# Vinduno-R-22-3-15.net
KiCad netlist of a schematic drawn in EAGLE
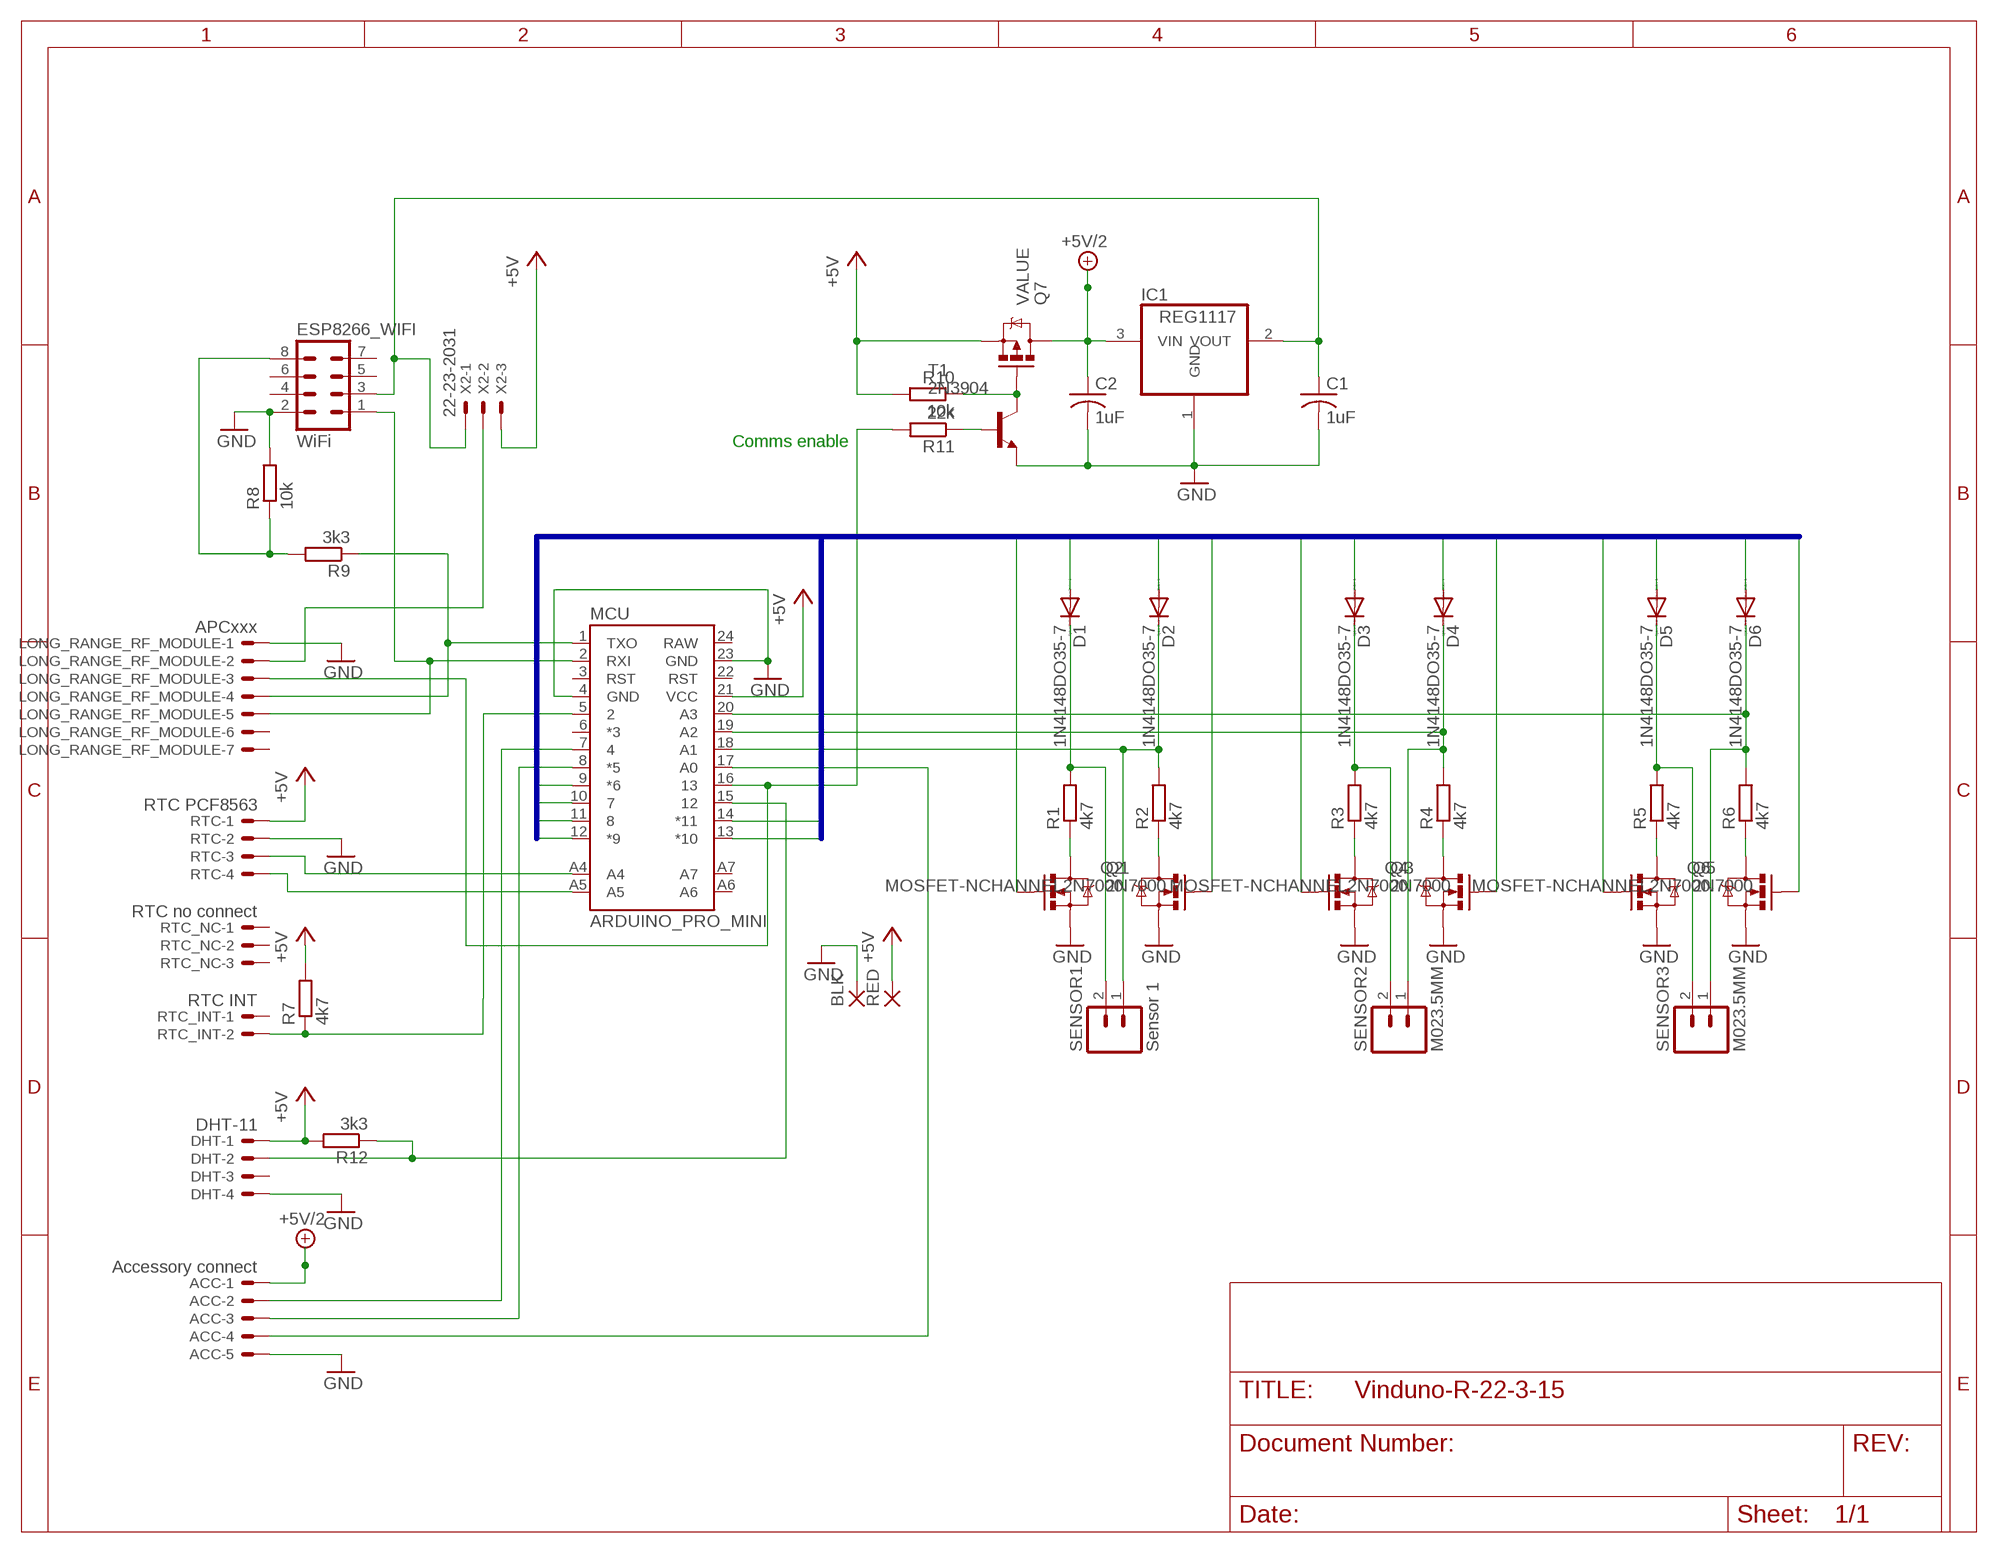
[diagram p0: schematic, sheet 1]

(export (version "E")
  (design (tool "Eeschema 10.0.6"))
  (components
    (comp (ref "ACC")
      (value "Accessory connect")
      (footprint "eagle-import:22-23-2051")
      (fields (field (name "MF") "MOLEX") (field (name "MPN") "22-23-2051"))
      (libsource (lib "eagle-import") (part "22-23-2051"))
    )
    (comp (ref "BLK")
      (value "WIREPAD2,54/0,9")
      (footprint "eagle-import:2,54_0,9")
      (libsource (lib "eagle-import") (part "WIREPAD2,54/0,9"))
    )
    (comp (ref "C1")
      (value "1uF")
      (footprint "eagle-import:C025-030X050")
      (libsource (lib "eagle-import") (part "C-US025-030X050"))
    )
    (comp (ref "C2")
      (value "1uF")
      (footprint "eagle-import:C025-030X050")
      (libsource (lib "eagle-import") (part "C-US025-030X050"))
    )
    (comp (ref "D1")
      (value "1N4148DO35-7")
      (footprint "eagle-import:DO35-7")
      (libsource (lib "eagle-import") (part "1N4148DO35-7"))
    )
    (comp (ref "D2")
      (value "1N4148DO35-7")
      (footprint "eagle-import:DO35-7")
      (libsource (lib "eagle-import") (part "1N4148DO35-7"))
    )
    (comp (ref "D3")
      (value "1N4148DO35-7")
      (footprint "eagle-import:DO35-7")
      (libsource (lib "eagle-import") (part "1N4148DO35-7"))
    )
    (comp (ref "D4")
      (value "1N4148DO35-7")
      (footprint "eagle-import:DO35-7")
      (libsource (lib "eagle-import") (part "1N4148DO35-7"))
    )
    (comp (ref "D5")
      (value "1N4148DO35-7")
      (footprint "eagle-import:DO35-7")
      (libsource (lib "eagle-import") (part "1N4148DO35-7"))
    )
    (comp (ref "D6")
      (value "1N4148DO35-7")
      (footprint "eagle-import:DO35-7")
      (libsource (lib "eagle-import") (part "1N4148DO35-7"))
    )
    (comp (ref "DHT")
      (value "DHT-11")
      (footprint "eagle-import:22-23-2041")
      (fields (field (name "MF") "MOLEX") (field (name "MPN") "22-23-2041"))
      (libsource (lib "eagle-import") (part "22-23-2041"))
    )
    (comp (ref "ESP8266_WIFI")
      (value "WiFi")
      (footprint "eagle-import:MA04-2")
      (libsource (lib "eagle-import") (part "MA04-2"))
    )
    (comp (ref "IC1")
      (value "REG1117")
      (footprint "eagle-import:SOT223")
      (libsource (lib "eagle-import") (part "REG1117"))
    )
    (comp (ref "LONG_RANGE_RF_MODULE")
      (value "APCxxx")
      (footprint "eagle-import:22-23-2071")
      (fields (field (name "MF") "MOLEX") (field (name "MPN") "22-23-2071"))
      (libsource (lib "eagle-import") (part "22-23-2071"))
    )
    (comp (ref "MCU")
      (value "ARDUINO_PRO_MINI")
      (footprint "eagle-import:ARDUINO_PRO_MINI")
      (libsource (lib "eagle-import") (part "ARDUINO_PRO_MINI"))
    )
    (comp (ref "Q1")
      (value "2N7000")
      (footprint "eagle-import:TO-92")
      (libsource (lib "eagle-import") (part "MOSFET-NCHANNEL2N7000"))
    )
    (comp (ref "Q2")
      (value "MOSFET-NCHANNEL2N7000")
      (footprint "eagle-import:TO-92")
      (libsource (lib "eagle-import") (part "MOSFET-NCHANNEL2N7000"))
    )
    (comp (ref "Q3")
      (value "2N7000")
      (footprint "eagle-import:TO-92")
      (libsource (lib "eagle-import") (part "MOSFET-NCHANNEL2N7000"))
    )
    (comp (ref "Q4")
      (value "MOSFET-NCHANNEL2N7000")
      (footprint "eagle-import:TO-92")
      (libsource (lib "eagle-import") (part "MOSFET-NCHANNEL2N7000"))
    )
    (comp (ref "Q5")
      (value "2N7000")
      (footprint "eagle-import:TO-92")
      (libsource (lib "eagle-import") (part "MOSFET-NCHANNEL2N7000"))
    )
    (comp (ref "Q6")
      (value "MOSFET-NCHANNEL2N7000")
      (footprint "eagle-import:TO-92")
      (libsource (lib "eagle-import") (part "MOSFET-NCHANNEL2N7000"))
    )
    (comp (ref "Q7")
      (value "AO3401")
      (footprint "eagle-import:SOT23-3")
      (libsource (lib "eagle-import") (part "MOSFET-PCHANNEL"))
    )
    (comp (ref "R1")
      (value "4k7")
      (footprint "eagle-import:0204_7")
      (libsource (lib "eagle-import") (part "R-EU_0204/7"))
    )
    (comp (ref "R2")
      (value "4k7")
      (footprint "eagle-import:0204_7")
      (libsource (lib "eagle-import") (part "R-EU_0204/7"))
    )
    (comp (ref "R3")
      (value "4k7")
      (footprint "eagle-import:0204_7")
      (libsource (lib "eagle-import") (part "R-EU_0204/7"))
    )
    (comp (ref "R4")
      (value "4k7")
      (footprint "eagle-import:0204_7")
      (libsource (lib "eagle-import") (part "R-EU_0204/7"))
    )
    (comp (ref "R5")
      (value "4k7")
      (footprint "eagle-import:0204_7")
      (libsource (lib "eagle-import") (part "R-EU_0204/7"))
    )
    (comp (ref "R6")
      (value "4k7")
      (footprint "eagle-import:0204_7")
      (libsource (lib "eagle-import") (part "R-EU_0204/7"))
    )
    (comp (ref "R7")
      (value "4k7")
      (footprint "eagle-import:0204_7")
      (libsource (lib "eagle-import") (part "R-EU_0204/7"))
    )
    (comp (ref "R8")
      (value "10k")
      (footprint "eagle-import:0204_7")
      (libsource (lib "eagle-import") (part "R-EU_0204/7"))
    )
    (comp (ref "R9")
      (value "3k3")
      (footprint "eagle-import:0204_7")
      (libsource (lib "eagle-import") (part "R-EU_0204/7"))
    )
    (comp (ref "R10")
      (value "10k")
      (footprint "eagle-import:0204_7")
      (libsource (lib "eagle-import") (part "R-EU_0204/7"))
    )
    (comp (ref "R11")
      (value "22k")
      (footprint "eagle-import:0204_7")
      (libsource (lib "eagle-import") (part "R-EU_0204/7"))
    )
    (comp (ref "R12")
      (value "3k3")
      (footprint "eagle-import:0204_7")
      (libsource (lib "eagle-import") (part "R-EU_0204/7"))
    )
    (comp (ref "RED")
      (value "WIREPAD2,54/0,9")
      (footprint "eagle-import:2,54_0,9")
      (libsource (lib "eagle-import") (part "WIREPAD2,54/0,9"))
    )
    (comp (ref "RTC")
      (value "RTC PCF8563")
      (footprint "eagle-import:22-23-2041")
      (fields (field (name "MF") "MOLEX") (field (name "MPN") "22-23-2041") (field (name "MPN_1") "RTC"))
      (libsource (lib "eagle-import") (part "22-23-2041"))
    )
    (comp (ref "RTC_INT")
      (value "RTC INT")
      (footprint "eagle-import:22-23-2021")
      (fields (field (name "MF") "MOLEX") (field (name "MPN") "22-23-2021"))
      (libsource (lib "eagle-import") (part "22-23-2021"))
    )
    (comp (ref "RTC_NC")
      (value "RTC no connect")
      (footprint "eagle-import:22-23-2031")
      (fields (field (name "MF") "MOLEX") (field (name "MPN") "22-23-2031"))
      (libsource (lib "eagle-import") (part "22-23-2031"))
    )
    (comp (ref "SENSOR1")
      (value "Sensor 1")
      (footprint "eagle-import:SCREWTERMINAL-3.5MM-2")
      (libsource (lib "eagle-import") (part "M023.5MM"))
    )
    (comp (ref "SENSOR2")
      (value "M023.5MM")
      (footprint "eagle-import:SCREWTERMINAL-3.5MM-2")
      (libsource (lib "eagle-import") (part "M023.5MM"))
    )
    (comp (ref "SENSOR3")
      (value "M023.5MM")
      (footprint "eagle-import:SCREWTERMINAL-3.5MM-2")
      (libsource (lib "eagle-import") (part "M023.5MM"))
    )
    (comp (ref "T1")
      (value "2N3904")
      (footprint "eagle-import:TO92")
      (libsource (lib "eagle-import") (part "2N3904"))
    )
    (comp (ref "X2")
      (value "22-23-2031")
      (footprint "eagle-import:22-23-2031")
      (fields (field (name "MF") "MOLEX"))
      (libsource (lib "eagle-import") (part "22-23-2031"))
    )
  )
  (nets
    (net (code "1") (name "+5V") (class "Default")
      (node (ref "DHT") (pin "1") (pinfunction "S_1") (pintype "passive"))
      (node (ref "MCU") (pin "21") (pinfunction "VCC_21") (pintype "bidirectional"))
      (node (ref "Q7") (pin "2") (pinfunction "S_2") (pintype "passive"))
      (node (ref "R10") (pin "2") (pinfunction "2_2") (pintype "passive"))
      (node (ref "R12") (pin "2") (pinfunction "2_2") (pintype "passive"))
      (node (ref "R7") (pin "2") (pinfunction "2_2") (pintype "passive"))
      (node (ref "RED") (pin "1") (pinfunction "P_1") (pintype "passive"))
      (node (ref "RTC") (pin "1") (pinfunction "S_1") (pintype "passive"))
      (node (ref "X2") (pin "3") (pinfunction "S_3") (pintype "passive"))
    )
    (net (code "2") (name "+5V{slash}2") (class "Default")
      (node (ref "ACC") (pin "1") (pinfunction "S_1") (pintype "passive"))
      (node (ref "C2") (pin "1") (pinfunction "1_1") (pintype "passive"))
      (node (ref "IC1") (pin "3") (pinfunction "VIN_3") (pintype "input"))
      (node (ref "Q7") (pin "3") (pinfunction "D_3") (pintype "passive"))
    )
    (net (code "3") (name "/DIODE1") (class "Default")
      (node (ref "D1") (pin "A") (pinfunction "A_A") (pintype "passive"))
      (node (ref "MCU") (pin "9") (pinfunction "*6_9") (pintype "bidirectional"))
      (node (ref "Q2") (pin "2") (pinfunction "G_2") (pintype "passive"))
    )
    (net (code "4") (name "/DIODE2") (class "Default")
      (node (ref "D2") (pin "A") (pinfunction "A_A") (pintype "passive"))
      (node (ref "MCU") (pin "10") (pinfunction "7_10") (pintype "bidirectional"))
      (node (ref "Q1") (pin "2") (pinfunction "G_2") (pintype "passive"))
    )
    (net (code "5") (name "/DIODE3") (class "Default")
      (node (ref "D3") (pin "A") (pinfunction "A_A") (pintype "passive"))
      (node (ref "MCU") (pin "11") (pinfunction "8_11") (pintype "bidirectional"))
      (node (ref "Q4") (pin "2") (pinfunction "G_2") (pintype "passive"))
    )
    (net (code "6") (name "/DIODE4") (class "Default")
      (node (ref "D4") (pin "A") (pinfunction "A_A") (pintype "passive"))
      (node (ref "MCU") (pin "12") (pinfunction "*9_12") (pintype "bidirectional"))
      (node (ref "Q3") (pin "2") (pinfunction "G_2") (pintype "passive"))
    )
    (net (code "7") (name "/DIODE5") (class "Default")
      (node (ref "D5") (pin "A") (pinfunction "A_A") (pintype "passive"))
      (node (ref "MCU") (pin "13") (pinfunction "*10_13") (pintype "bidirectional"))
      (node (ref "Q6") (pin "2") (pinfunction "G_2") (pintype "passive"))
    )
    (net (code "8") (name "/DIODE6") (class "Default")
      (node (ref "D6") (pin "A") (pinfunction "A_A") (pintype "passive"))
      (node (ref "MCU") (pin "14") (pinfunction "*11_14") (pintype "bidirectional"))
      (node (ref "Q5") (pin "2") (pinfunction "G_2") (pintype "passive"))
    )
    (net (code "9") (name "GND") (class "Default")
      (node (ref "ACC") (pin "5") (pinfunction "S_5") (pintype "passive"))
      (node (ref "BLK") (pin "1") (pinfunction "P_1") (pintype "passive"))
      (node (ref "C1") (pin "2") (pinfunction "2_2") (pintype "passive"))
      (node (ref "C2") (pin "2") (pinfunction "2_2") (pintype "passive"))
      (node (ref "DHT") (pin "4") (pinfunction "S_4") (pintype "passive"))
      (node (ref "ESP8266_WIFI") (pin "2") (pinfunction "2_2") (pintype "passive"))
      (node (ref "IC1") (pin "1") (pinfunction "GND_1") (pintype "power_in"))
      (node (ref "LONG_RANGE_RF_MODULE") (pin "1") (pinfunction "S_1") (pintype "passive"))
      (node (ref "MCU") (pin "23") (pinfunction "GND_23") (pintype "bidirectional"))
      (node (ref "MCU") (pin "4") (pinfunction "GND_4") (pintype "bidirectional"))
      (node (ref "Q1") (pin "1") (pinfunction "S_1") (pintype "passive"))
      (node (ref "Q2") (pin "1") (pinfunction "S_1") (pintype "passive"))
      (node (ref "Q3") (pin "1") (pinfunction "S_1") (pintype "passive"))
      (node (ref "Q4") (pin "1") (pinfunction "S_1") (pintype "passive"))
      (node (ref "Q5") (pin "1") (pinfunction "S_1") (pintype "passive"))
      (node (ref "Q6") (pin "1") (pinfunction "S_1") (pintype "passive"))
      (node (ref "R8") (pin "2") (pinfunction "2_2") (pintype "passive"))
      (node (ref "RTC") (pin "2") (pinfunction "S_2") (pintype "passive"))
      (node (ref "T1") (pin "3") (pinfunction "E_3") (pintype "passive"))
    )
    (net (code "10") (name "Net-(ACCB-S)") (class "Default")
      (node (ref "ACC") (pin "2") (pinfunction "S_2") (pintype "passive"))
      (node (ref "MCU") (pin "7") (pinfunction "4_7") (pintype "bidirectional"))
    )
    (net (code "11") (name "Net-(ACCC-S)") (class "Default")
      (node (ref "ACC") (pin "3") (pinfunction "S_3") (pintype "passive"))
      (node (ref "MCU") (pin "8") (pinfunction "*5_8") (pintype "bidirectional"))
    )
    (net (code "12") (name "Net-(ACCD-S)") (class "Default")
      (node (ref "ACC") (pin "4") (pinfunction "S_4") (pintype "passive"))
      (node (ref "MCU") (pin "17") (pinfunction "A0_17") (pintype "bidirectional"))
    )
    (net (code "13") (name "Net-(D1-PadC)") (class "Default")
      (node (ref "D1") (pin "C") (pinfunction "C_C") (pintype "passive"))
      (node (ref "R1") (pin "2") (pinfunction "2_2") (pintype "passive"))
      (node (ref "SENSOR1") (pin "2") (pinfunction "2_2") (pintype "passive"))
    )
    (net (code "14") (name "Net-(D3-PadC)") (class "Default")
      (node (ref "D3") (pin "C") (pinfunction "C_C") (pintype "passive"))
      (node (ref "R3") (pin "2") (pinfunction "2_2") (pintype "passive"))
      (node (ref "SENSOR2") (pin "2") (pinfunction "2_2") (pintype "passive"))
    )
    (net (code "15") (name "Net-(D5-PadC)") (class "Default")
      (node (ref "D5") (pin "C") (pinfunction "C_C") (pintype "passive"))
      (node (ref "R5") (pin "2") (pinfunction "2_2") (pintype "passive"))
      (node (ref "SENSOR3") (pin "2") (pinfunction "2_2") (pintype "passive"))
    )
    (net (code "16") (name "Net-(DHTB-S)") (class "Default")
      (node (ref "DHT") (pin "2") (pinfunction "S_2") (pintype "passive"))
      (node (ref "MCU") (pin "15") (pinfunction "12_15") (pintype "bidirectional"))
      (node (ref "R12") (pin "1") (pinfunction "1_1") (pintype "passive"))
    )
    (net (code "17") (name "Net-(ESP8266_WIFI-Pad8)") (class "Default")
      (node (ref "ESP8266_WIFI") (pin "8") (pinfunction "8_8") (pintype "passive"))
      (node (ref "R8") (pin "1") (pinfunction "1_1") (pintype "passive"))
      (node (ref "R9") (pin "2") (pinfunction "2_2") (pintype "passive"))
    )
    (net (code "18") (name "Net-(IC1-VOUT)") (class "Default")
      (node (ref "C1") (pin "1") (pinfunction "1_1") (pintype "passive"))
      (node (ref "ESP8266_WIFI") (pin "3") (pinfunction "3_3") (pintype "passive"))
      (node (ref "IC1") (pin "2") (pinfunction "VOUT_2") (pintype "output"))
      (node (ref "X2") (pin "1") (pinfunction "S_1") (pintype "passive"))
    )
    (net (code "19") (name "Net-(LONG_RANGE_RF_MODULEB-S)") (class "Default")
      (node (ref "LONG_RANGE_RF_MODULE") (pin "2") (pinfunction "S_2") (pintype "passive"))
      (node (ref "X2") (pin "2") (pinfunction "S_2") (pintype "passive"))
    )
    (net (code "20") (name "Net-(LONG_RANGE_RF_MODULEC-S)") (class "Default")
      (node (ref "LONG_RANGE_RF_MODULE") (pin "3") (pinfunction "S_3") (pintype "passive"))
      (node (ref "MCU") (pin "16") (pinfunction "13_16") (pintype "bidirectional"))
      (node (ref "R11") (pin "2") (pinfunction "2_2") (pintype "passive"))
    )
    (net (code "21") (name "Net-(LONG_RANGE_RF_MODULED-S)") (class "Default")
      (node (ref "LONG_RANGE_RF_MODULE") (pin "4") (pinfunction "S_4") (pintype "passive"))
      (node (ref "MCU") (pin "1") (pinfunction "TXO_1") (pintype "bidirectional"))
      (node (ref "R9") (pin "1") (pinfunction "1_1") (pintype "passive"))
    )
    (net (code "22") (name "Net-(LONG_RANGE_RF_MODULEE-S)") (class "Default")
      (node (ref "ESP8266_WIFI") (pin "1") (pinfunction "1_1") (pintype "passive"))
      (node (ref "LONG_RANGE_RF_MODULE") (pin "5") (pinfunction "S_5") (pintype "passive"))
      (node (ref "MCU") (pin "2") (pinfunction "RXI_2") (pintype "bidirectional"))
    )
    (net (code "23") (name "Net-(MCU-2)") (class "Default")
      (node (ref "MCU") (pin "5") (pinfunction "2_5") (pintype "bidirectional"))
      (node (ref "R7") (pin "1") (pinfunction "1_1") (pintype "passive"))
      (node (ref "RTC_INT") (pin "2") (pinfunction "S_2") (pintype "passive"))
    )
    (net (code "24") (name "Net-(MCU-A1)") (class "Default")
      (node (ref "D2") (pin "C") (pinfunction "C_C") (pintype "passive"))
      (node (ref "MCU") (pin "18") (pinfunction "A1_18") (pintype "bidirectional"))
      (node (ref "R2") (pin "2") (pinfunction "2_2") (pintype "passive"))
      (node (ref "SENSOR1") (pin "1") (pinfunction "1_1") (pintype "passive"))
    )
    (net (code "25") (name "Net-(MCU-A2)") (class "Default")
      (node (ref "D4") (pin "C") (pinfunction "C_C") (pintype "passive"))
      (node (ref "MCU") (pin "19") (pinfunction "A2_19") (pintype "bidirectional"))
      (node (ref "R4") (pin "2") (pinfunction "2_2") (pintype "passive"))
      (node (ref "SENSOR2") (pin "1") (pinfunction "1_1") (pintype "passive"))
    )
    (net (code "26") (name "Net-(MCU-A3)") (class "Default")
      (node (ref "D6") (pin "C") (pinfunction "C_C") (pintype "passive"))
      (node (ref "MCU") (pin "20") (pinfunction "A3_20") (pintype "bidirectional"))
      (node (ref "R6") (pin "2") (pinfunction "2_2") (pintype "passive"))
      (node (ref "SENSOR3") (pin "1") (pinfunction "1_1") (pintype "passive"))
    )
    (net (code "27") (name "Net-(Q1-D)") (class "Default")
      (node (ref "Q1") (pin "3") (pinfunction "D_3") (pintype "passive"))
      (node (ref "R1") (pin "1") (pinfunction "1_1") (pintype "passive"))
    )
    (net (code "28") (name "Net-(Q2-D)") (class "Default")
      (node (ref "Q2") (pin "3") (pinfunction "D_3") (pintype "passive"))
      (node (ref "R2") (pin "1") (pinfunction "1_1") (pintype "passive"))
    )
    (net (code "29") (name "Net-(Q3-D)") (class "Default")
      (node (ref "Q3") (pin "3") (pinfunction "D_3") (pintype "passive"))
      (node (ref "R3") (pin "1") (pinfunction "1_1") (pintype "passive"))
    )
    (net (code "30") (name "Net-(Q4-D)") (class "Default")
      (node (ref "Q4") (pin "3") (pinfunction "D_3") (pintype "passive"))
      (node (ref "R4") (pin "1") (pinfunction "1_1") (pintype "passive"))
    )
    (net (code "31") (name "Net-(Q5-D)") (class "Default")
      (node (ref "Q5") (pin "3") (pinfunction "D_3") (pintype "passive"))
      (node (ref "R5") (pin "1") (pinfunction "1_1") (pintype "passive"))
    )
    (net (code "32") (name "Net-(Q6-D)") (class "Default")
      (node (ref "Q6") (pin "3") (pinfunction "D_3") (pintype "passive"))
      (node (ref "R6") (pin "1") (pinfunction "1_1") (pintype "passive"))
    )
    (net (code "33") (name "Net-(Q7-G)") (class "Default")
      (node (ref "Q7") (pin "1") (pinfunction "G_1") (pintype "passive"))
      (node (ref "R10") (pin "1") (pinfunction "1_1") (pintype "passive"))
      (node (ref "T1") (pin "1") (pinfunction "C_1") (pintype "passive"))
    )
    (net (code "34") (name "Net-(RTCC-S)") (class "Default")
      (node (ref "MCU") (pin "A4") (pinfunction "A4_A4") (pintype "bidirectional"))
      (node (ref "RTC") (pin "3") (pinfunction "S_3") (pintype "passive"))
    )
    (net (code "35") (name "Net-(RTCD-S)") (class "Default")
      (node (ref "MCU") (pin "A5") (pinfunction "A5_A5") (pintype "bidirectional"))
      (node (ref "RTC") (pin "4") (pinfunction "S_4") (pintype "passive"))
    )
    (net (code "36") (name "Net-(T1-B)") (class "Default")
      (node (ref "R11") (pin "1") (pinfunction "1_1") (pintype "passive"))
      (node (ref "T1") (pin "2") (pinfunction "B_2") (pintype "passive"))
    )
    (net (code "37") (name "unconnected-(DHTC-S-Pad3)") (class "Default")
      (node (ref "DHT") (pin "3") (pinfunction "S_3") (pintype "passive"))
    )
    (net (code "38") (name "unconnected-(ESP8266_WIFI-Pad4)") (class "Default")
      (node (ref "ESP8266_WIFI") (pin "4") (pinfunction "4_4") (pintype "passive"))
    )
    (net (code "39") (name "unconnected-(ESP8266_WIFI-Pad5)") (class "Default")
      (node (ref "ESP8266_WIFI") (pin "5") (pinfunction "5_5") (pintype "passive"))
    )
    (net (code "40") (name "unconnected-(ESP8266_WIFI-Pad6)") (class "Default")
      (node (ref "ESP8266_WIFI") (pin "6") (pinfunction "6_6") (pintype "passive"))
    )
    (net (code "41") (name "unconnected-(ESP8266_WIFI-Pad7)") (class "Default")
      (node (ref "ESP8266_WIFI") (pin "7") (pinfunction "7_7") (pintype "passive"))
    )
    (net (code "42") (name "unconnected-(LONG_RANGE_RF_MODULEF-S-Pad6)") (class "Default")
      (node (ref "LONG_RANGE_RF_MODULE") (pin "6") (pinfunction "S_6") (pintype "passive"))
    )
    (net (code "43") (name "unconnected-(LONG_RANGE_RF_MODULEG-S-Pad7)") (class "Default")
      (node (ref "LONG_RANGE_RF_MODULE") (pin "7") (pinfunction "S_7") (pintype "passive"))
    )
    (net (code "44") (name "unconnected-(MCU-*3-Pad6)") (class "Default")
      (node (ref "MCU") (pin "6") (pinfunction "*3_6") (pintype "bidirectional"))
    )
    (net (code "45") (name "unconnected-(MCU-PadA6)") (class "Default")
      (node (ref "MCU") (pin "A6") (pinfunction "A6_A6") (pintype "bidirectional"))
    )
    (net (code "46") (name "unconnected-(MCU-PadA7)") (class "Default")
      (node (ref "MCU") (pin "A7") (pinfunction "A7_A7") (pintype "bidirectional"))
    )
    (net (code "47") (name "unconnected-(MCU-RAW-Pad24)") (class "Default")
      (node (ref "MCU") (pin "24") (pinfunction "RAW_24") (pintype "bidirectional"))
    )
    (net (code "48") (name "unconnected-(MCU-RST-Pad3)") (class "Default")
      (node (ref "MCU") (pin "3") (pinfunction "RST_3") (pintype "bidirectional"))
    )
    (net (code "49") (name "unconnected-(MCU-RST-Pad22)") (class "Default")
      (node (ref "MCU") (pin "22") (pinfunction "RST_22") (pintype "bidirectional"))
    )
    (net (code "50") (name "unconnected-(RTC_INTA-S-Pad1)") (class "Default")
      (node (ref "RTC_INT") (pin "1") (pinfunction "S_1") (pintype "passive"))
    )
    (net (code "51") (name "unconnected-(RTC_NCA-S-Pad1)") (class "Default")
      (node (ref "RTC_NC") (pin "1") (pinfunction "S_1") (pintype "passive"))
    )
    (net (code "52") (name "unconnected-(RTC_NCB-S-Pad2)") (class "Default")
      (node (ref "RTC_NC") (pin "2") (pinfunction "S_2") (pintype "passive"))
    )
    (net (code "53") (name "unconnected-(RTC_NCC-S-Pad3)") (class "Default")
      (node (ref "RTC_NC") (pin "3") (pinfunction "S_3") (pintype "passive"))
    )
  )
)
